# E17-12-VCU-TPC.net
KiCad netlist of a schematic drawn in Altium Designer
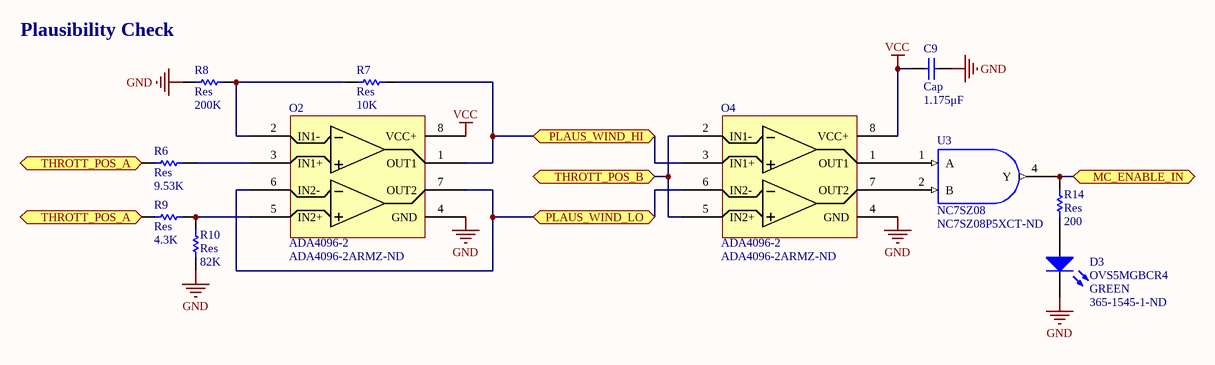
[diagram p0: E17-12-VCU-TPC.SchDoc]

(export (version "E")
  (design (tool "Eeschema 10.0.6"))
  (components
    (comp (ref "C9")
      (value "Cap")
      (footprint "C0805")
      (description "Capacitor")
      (fields (field (name "ALTIUM_VALUE") "1.175μF") (field (name "PUBLISHER") "Altium Limited"))
      (libsource (lib "Capacitors") (part "Cap"))
    )
    (comp (ref "D3")
      (value "OVS5MGBCR4")
      (footprint "OVS5MGBCR4")
      (description "Typical GREEN LED")
      (fields
        (field (name "COLOUR") "GREEN")
        (field (name "SUPPLIER PART NUMBER 1") "365-1545-1-ND")
        (field (name "PUBLISHER") "Altium Limited")
      )
      (libsource (lib "LEDs") (part "OVS5MGBCR4"))
    )
    (comp (ref "O2")
      (value "ADA4096-2")
      (footprint "TSSOP8")
      (description "2 Op-Amps, 8-TSSOP, 32V Overvoltage Protection")
      (fields (field (name "SUPPLIER PART NUMBER 1") "ADA4096-2ARMZ-ND"))
      (libsource (lib "Operational Amplifiers") (part "ADA4096-2"))
    )
    (comp (ref "O4")
      (value "ADA4096-2")
      (footprint "TSSOP8")
      (description "2 Op-Amps, 8-TSSOP, 32V Overvoltage Protection")
      (fields (field (name "SUPPLIER PART NUMBER 1") "ADA4096-2ARMZ-ND"))
      (libsource (lib "Operational Amplifiers") (part "ADA4096-2"))
    )
    (comp (ref "R6")
      (value "Res")
      (footprint "2012[0805]")
      (description "Surface Mount Resistor")
      (fields (field (name "ALTIUM_VALUE") "9.53K") (field (name "PUBLISHER") "Altium Limited"))
      (libsource (lib "Resistors") (part "Res"))
    )
    (comp (ref "R7")
      (value "Res")
      (footprint "2012[0805]")
      (description "Surface Mount Resistor")
      (fields (field (name "ALTIUM_VALUE") "10K") (field (name "PUBLISHER") "Altium Limited"))
      (libsource (lib "Resistors") (part "Res"))
    )
    (comp (ref "R8")
      (value "Res")
      (footprint "2012[0805]")
      (description "Surface Mount Resistor")
      (fields (field (name "ALTIUM_VALUE") "200K") (field (name "PUBLISHER") "Altium Limited"))
      (libsource (lib "Resistors") (part "Res"))
    )
    (comp (ref "R9")
      (value "Res")
      (footprint "2012[0805]")
      (description "Surface Mount Resistor")
      (fields (field (name "ALTIUM_VALUE") "4.3K") (field (name "PUBLISHER") "Altium Limited"))
      (libsource (lib "Resistors") (part "Res"))
    )
    (comp (ref "R10")
      (value "Res")
      (footprint "2012[0805]")
      (description "Surface Mount Resistor")
      (fields (field (name "ALTIUM_VALUE") "82K") (field (name "PUBLISHER") "Altium Limited"))
      (libsource (lib "Resistors") (part "Res"))
    )
    (comp (ref "R14")
      (value "Res")
      (footprint "2012[0805]")
      (description "Surface Mount Resistor")
      (fields (field (name "ALTIUM_VALUE") "200") (field (name "PUBLISHER") "Altium Limited"))
      (libsource (lib "Resistors") (part "Res"))
    )
    (comp (ref "U3")
      (value "NC7SZ08")
      (footprint "SOT95P280X145-5N")
      (fields (field (name "SUPPLIER PART NUMBER 1") "NC7SZ08P5XCT-ND"))
      (libsource (lib "Logic Gates") (part "NC7SZ08"))
    )
  )
  (nets
    (net (code "1") (name "/MC_ENABLE_IN") (class "Default")
      (node (ref "R14") (pin "2") (pinfunction "2_2") (pintype "passive"))
      (node (ref "U3") (pin "4") (pinfunction "Y_4") (pintype "output"))
    )
    (net (code "2") (name "/PLAUS_WIND_HI") (class "Default")
      (node (ref "O2") (pin "1") (pinfunction "OUT1_1") (pintype "passive"))
      (node (ref "O4") (pin "3") (pinfunction "IN1+_3") (pintype "passive"))
      (node (ref "R7") (pin "2") (pinfunction "2_2") (pintype "passive"))
    )
    (net (code "3") (name "/PLAUS_WIND_LO") (class "Default")
      (node (ref "O2") (pin "6") (pinfunction "IN2-_6") (pintype "passive"))
      (node (ref "O2") (pin "7") (pinfunction "OUT2_7") (pintype "passive"))
      (node (ref "O4") (pin "6") (pinfunction "IN2-_6") (pintype "passive"))
    )
    (net (code "4") (name "/THROTT_POS_A") (class "Default")
      (node (ref "R6") (pin "2") (pinfunction "2_2") (pintype "passive"))
      (node (ref "R9") (pin "2") (pinfunction "2_2") (pintype "passive"))
    )
    (net (code "5") (name "/THROTT_POS_B") (class "Default")
      (node (ref "O4") (pin "2") (pinfunction "IN1-_2") (pintype "passive"))
      (node (ref "O4") (pin "5") (pinfunction "IN2+_5") (pintype "passive"))
    )
    (net (code "6") (name "GND") (class "Default")
      (node (ref "C9") (pin "1") (pinfunction "1_1") (pintype "passive"))
      (node (ref "D3") (pin "2") (pinfunction "K_2") (pintype "passive"))
      (node (ref "O2") (pin "4") (pinfunction "GND_4") (pintype "passive"))
      (node (ref "O4") (pin "4") (pinfunction "GND_4") (pintype "passive"))
      (node (ref "R10") (pin "1") (pinfunction "1_1") (pintype "passive"))
      (node (ref "R8") (pin "1") (pinfunction "1_1") (pintype "passive"))
      (node (ref "U3") (pin "3") (pinfunction "GND_3") (pintype "power_in"))
    )
    (net (code "7") (name "Net-(D3-A)") (class "Default")
      (node (ref "D3") (pin "1") (pinfunction "A_1") (pintype "passive"))
      (node (ref "R14") (pin "1") (pinfunction "1_1") (pintype "passive"))
    )
    (net (code "8") (name "Net-(O2-IN1+)") (class "Default")
      (node (ref "O2") (pin "3") (pinfunction "IN1+_3") (pintype "passive"))
      (node (ref "R6") (pin "1") (pinfunction "1_1") (pintype "passive"))
    )
    (net (code "9") (name "Net-(O2-IN1-)") (class "Default")
      (node (ref "O2") (pin "2") (pinfunction "IN1-_2") (pintype "passive"))
      (node (ref "R7") (pin "1") (pinfunction "1_1") (pintype "passive"))
      (node (ref "R8") (pin "2") (pinfunction "2_2") (pintype "passive"))
    )
    (net (code "10") (name "Net-(O2-IN2+)") (class "Default")
      (node (ref "O2") (pin "5") (pinfunction "IN2+_5") (pintype "passive"))
      (node (ref "R10") (pin "2") (pinfunction "2_2") (pintype "passive"))
      (node (ref "R9") (pin "1") (pinfunction "1_1") (pintype "passive"))
    )
    (net (code "11") (name "Net-(O4-OUT1)") (class "Default")
      (node (ref "O4") (pin "1") (pinfunction "OUT1_1") (pintype "passive"))
      (node (ref "U3") (pin "1") (pinfunction "A_1") (pintype "input"))
    )
    (net (code "12") (name "Net-(O4-OUT2)") (class "Default")
      (node (ref "O4") (pin "7") (pinfunction "OUT2_7") (pintype "passive"))
      (node (ref "U3") (pin "2") (pinfunction "B_2") (pintype "input"))
    )
    (net (code "13") (name "VCC") (class "Default")
      (node (ref "C9") (pin "2") (pinfunction "2_2") (pintype "passive"))
      (node (ref "O2") (pin "8") (pinfunction "VCC+_8") (pintype "passive"))
      (node (ref "O4") (pin "8") (pinfunction "VCC+_8") (pintype "passive"))
      (node (ref "U3") (pin "5") (pinfunction "VCC_5") (pintype "power_in"))
    )
  )
)
